# schematic.net
KiCad netlist of a schematic drawn in EAGLE
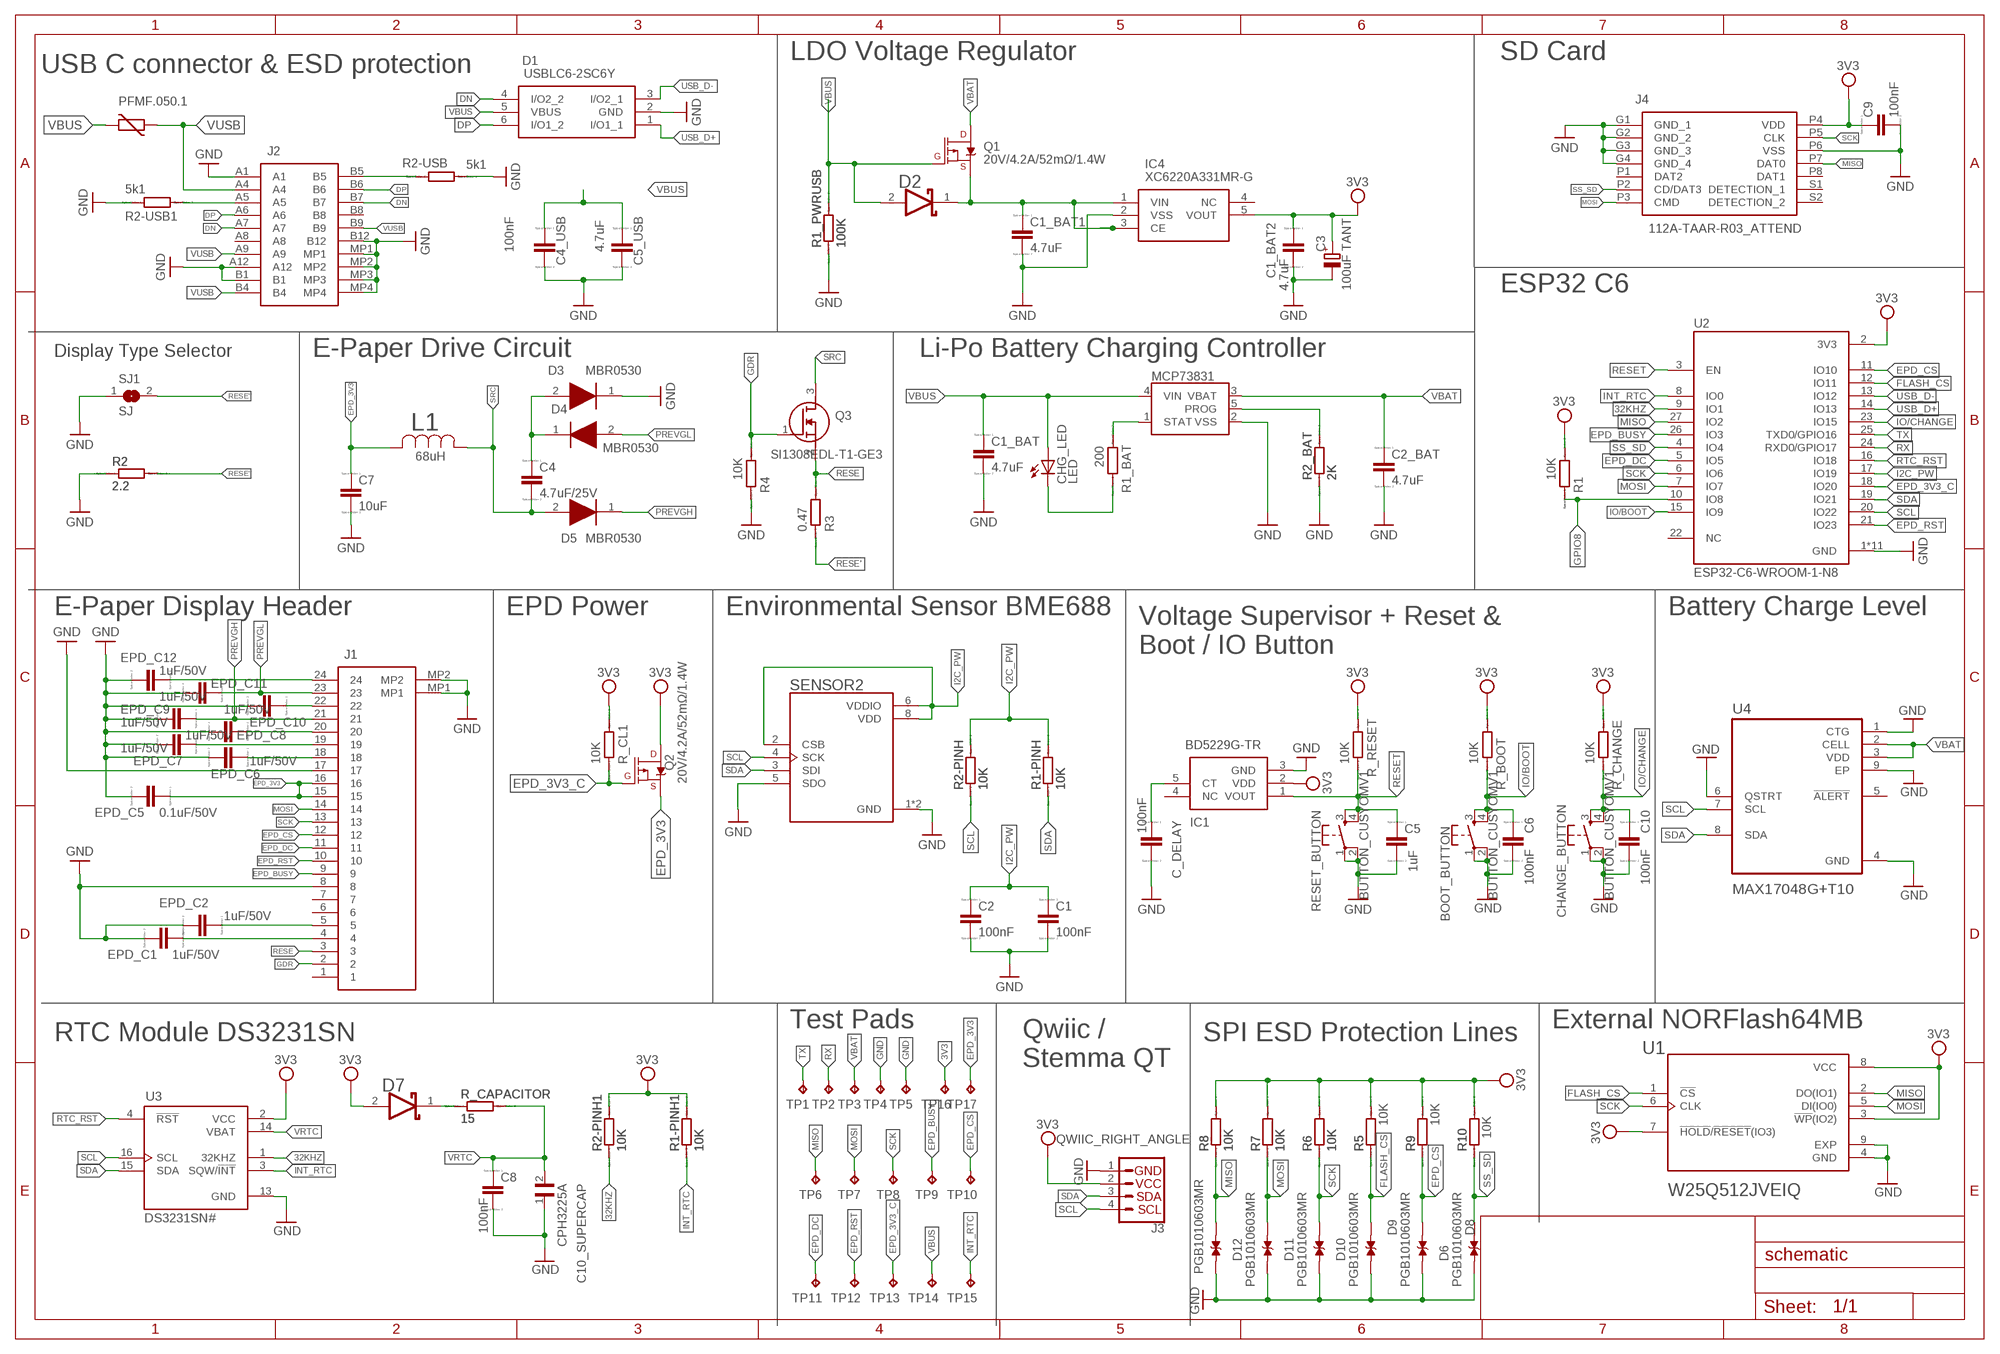
[diagram p0: schematic, sheet 1]

(export (version "E")
  (design (tool "Eeschema 10.0.6"))
  (components
    (comp (ref "BOOT_BUTTON")
      (value "BUTTON_CUSYOMV1")
      (footprint "eagle-import:MYBUTTON")
      (libsource (lib "eagle-import") (part "BUTTON_CUSYOMV1"))
    )
    (comp (ref "C1")
      (value "100nF")
      (footprint "eagle-import:EAGLE-LTSPICE_C0402")
      (libsource (lib "eagle-import") (part "EAGLE-LTSPICE_CC0402"))
    )
    (comp (ref "C1_BAT")
      (value "4.7uF")
      (footprint "eagle-import:EAGLE-LTSPICE_C0402")
      (libsource (lib "eagle-import") (part "EAGLE-LTSPICE_CC0402"))
    )
    (comp (ref "C1_BAT1")
      (value "4.7uF")
      (footprint "eagle-import:EAGLE-LTSPICE_C0402")
      (libsource (lib "eagle-import") (part "EAGLE-LTSPICE_CC0402"))
    )
    (comp (ref "C1_BAT2")
      (value "4.7uF")
      (footprint "eagle-import:EAGLE-LTSPICE_C0402")
      (libsource (lib "eagle-import") (part "EAGLE-LTSPICE_CC0402"))
    )
    (comp (ref "C2")
      (value "100nF")
      (footprint "eagle-import:EAGLE-LTSPICE_C0402")
      (libsource (lib "eagle-import") (part "EAGLE-LTSPICE_CC0402"))
    )
    (comp (ref "C2_BAT")
      (value "4.7uF")
      (footprint "eagle-import:EAGLE-LTSPICE_C0402")
      (libsource (lib "eagle-import") (part "EAGLE-LTSPICE_CC0402"))
    )
    (comp (ref "C3")
      (value "100uF TANT")
      (footprint "eagle-import:RCL_CT3528")
      (libsource (lib "eagle-import") (part "RCL_CPOL-EUCT3528"))
    )
    (comp (ref "C4")
      (value "4.7uF/25V")
      (footprint "eagle-import:EAGLE-LTSPICE_C0402")
      (libsource (lib "eagle-import") (part "EAGLE-LTSPICE_CC0402"))
    )
    (comp (ref "C4_USB")
      (value "100nF")
      (footprint "eagle-import:EAGLE-LTSPICE_C0402")
      (libsource (lib "eagle-import") (part "EAGLE-LTSPICE_CC0402"))
    )
    (comp (ref "C5")
      (value "1uF")
      (footprint "eagle-import:EAGLE-LTSPICE_C0402")
      (libsource (lib "eagle-import") (part "EAGLE-LTSPICE_CC0402"))
    )
    (comp (ref "C5_USB")
      (value "4.7uF")
      (footprint "eagle-import:EAGLE-LTSPICE_C0402")
      (libsource (lib "eagle-import") (part "EAGLE-LTSPICE_CC0402"))
    )
    (comp (ref "C6")
      (value "100nF")
      (footprint "eagle-import:EAGLE-LTSPICE_C0402")
      (libsource (lib "eagle-import") (part "EAGLE-LTSPICE_CC0402"))
    )
    (comp (ref "C7")
      (value "10uF")
      (footprint "eagle-import:EAGLE-LTSPICE_C0402")
      (libsource (lib "eagle-import") (part "EAGLE-LTSPICE_CC0402"))
    )
    (comp (ref "C8")
      (value "100nF")
      (footprint "eagle-import:EAGLE-LTSPICE_C0402")
      (libsource (lib "eagle-import") (part "EAGLE-LTSPICE_CC0402"))
    )
    (comp (ref "C9")
      (value "100nF")
      (footprint "eagle-import:EAGLE-LTSPICE_C0402")
      (libsource (lib "eagle-import") (part "EAGLE-LTSPICE_CC0402"))
    )
    (comp (ref "C10")
      (value "100nF")
      (footprint "eagle-import:EAGLE-LTSPICE_C0402")
      (libsource (lib "eagle-import") (part "EAGLE-LTSPICE_CC0402"))
    )
    (comp (ref "C10_SUPERCAP")
      (value "CPH3225A")
      (footprint "eagle-import:CAPCP3225X100N")
      (fields (field (name "MF") "Seiko Instruments"))
      (libsource (lib "eagle-import") (part "CPH3225A"))
    )
    (comp (ref "CHANGE_BUTTON")
      (value "BUTTON_CUSYOMV1")
      (footprint "eagle-import:MYBUTTON")
      (libsource (lib "eagle-import") (part "BUTTON_CUSYOMV1"))
    )
    (comp (ref "CHG_LED")
      (value "LED")
      (footprint "eagle-import:ADAFRUIT_CHIP-LED0603")
      (libsource (lib "eagle-import") (part "ADAFRUIT_LEDCHIP-LED0603"))
    )
    (comp (ref "C_DELAY")
      (value "100nF")
      (footprint "eagle-import:EAGLE-LTSPICE_C0402")
      (libsource (lib "eagle-import") (part "EAGLE-LTSPICE_CC0402"))
    )
    (comp (ref "D1")
      (value "USBLC6-2SC6Y")
      (footprint "eagle-import:SOT95P280X145-6N")
      (fields (field (name "MF") "STMicroelectronics"))
      (libsource (lib "eagle-import") (part "USBLC6-2SC6Y"))
    )
    (comp (ref "D2")
      (value "ESP32_WROVER_AVX---SD0805S020S1R0_AVX_SD0805S020S1R0_0_0AVX_SD0805S020S1R0_0_0")
      (footprint "eagle-import:ESP32_WROVER_AVX---SD0805S020S1R0_AVX_SD0805S020S1R0_0")
      (fields
        (field (name "DIGIKEY_PART_NUMBER") "478-7800-1-ND")
        (field (name "MF") "AVX")
        (field (name "MOUSER_PART_NUMBER") "581-SD0805S020S1R0")
      )
      (libsource (lib "eagle-import") (part "ESP32_WROVER_AVX---SD0805S020S1R0_AVX_SD0805S020S1R0_0_0AVX_SD0805S020S1R0_0_0"))
    )
    (comp (ref "D3")
      (value "MBR0530")
      (footprint "eagle-import:SOD3716X135N")
      (fields (field (name "MF") "ON Semiconductor"))
      (libsource (lib "eagle-import") (part "MBR0530"))
    )
    (comp (ref "D4")
      (value "MBR0530")
      (footprint "eagle-import:SOD3716X135N")
      (fields (field (name "MF") "ON Semiconductor"))
      (libsource (lib "eagle-import") (part "MBR0530"))
    )
    (comp (ref "D5")
      (value "MBR0530")
      (footprint "eagle-import:SOD3716X135N")
      (fields (field (name "MF") "ON Semiconductor"))
      (libsource (lib "eagle-import") (part "MBR0530"))
    )
    (comp (ref "D6")
      (value "PGB1010603MR")
      (footprint "eagle-import:DIOC1608X36N")
      (fields (field (name "MF") "Littelfuse Inc."))
      (libsource (lib "eagle-import") (part "PGB1010603MR"))
    )
    (comp (ref "D7")
      (value "ESP32_WROVER_AVX---SD0805S020S1R0_AVX_SD0805S020S1R0_0_0AVX_SD0805S020S1R0_0_0")
      (footprint "eagle-import:ESP32_WROVER_AVX---SD0805S020S1R0_AVX_SD0805S020S1R0_0")
      (fields
        (field (name "DIGIKEY_PART_NUMBER") "478-7800-1-ND")
        (field (name "MF") "AVX")
        (field (name "MOUSER_PART_NUMBER") "581-SD0805S020S1R0")
      )
      (libsource (lib "eagle-import") (part "ESP32_WROVER_AVX---SD0805S020S1R0_AVX_SD0805S020S1R0_0_0AVX_SD0805S020S1R0_0_0"))
    )
    (comp (ref "D8")
      (value "PGB1010603MR")
      (footprint "eagle-import:DIOC1608X36N")
      (fields (field (name "MF") "Littelfuse Inc."))
      (libsource (lib "eagle-import") (part "PGB1010603MR"))
    )
    (comp (ref "D9")
      (value "PGB1010603MR")
      (footprint "eagle-import:DIOC1608X36N")
      (fields (field (name "MF") "Littelfuse Inc."))
      (libsource (lib "eagle-import") (part "PGB1010603MR"))
    )
    (comp (ref "D10")
      (value "PGB1010603MR")
      (footprint "eagle-import:DIOC1608X36N")
      (fields (field (name "MF") "Littelfuse Inc."))
      (libsource (lib "eagle-import") (part "PGB1010603MR"))
    )
    (comp (ref "D11")
      (value "PGB1010603MR")
      (footprint "eagle-import:DIOC1608X36N")
      (fields (field (name "MF") "Littelfuse Inc."))
      (libsource (lib "eagle-import") (part "PGB1010603MR"))
    )
    (comp (ref "D12")
      (value "PGB1010603MR")
      (footprint "eagle-import:DIOC1608X36N")
      (fields (field (name "MF") "Littelfuse Inc."))
      (libsource (lib "eagle-import") (part "PGB1010603MR"))
    )
    (comp (ref "EPD_C1")
      (value "1uF/50V")
      (footprint "eagle-import:EAGLE-LTSPICE_C0402")
      (libsource (lib "eagle-import") (part "EAGLE-LTSPICE_CC0402"))
    )
    (comp (ref "EPD_C2")
      (value "1uF/50V")
      (footprint "eagle-import:EAGLE-LTSPICE_C0402")
      (libsource (lib "eagle-import") (part "EAGLE-LTSPICE_CC0402"))
    )
    (comp (ref "EPD_C5")
      (value "0.1uF/50V")
      (footprint "eagle-import:EAGLE-LTSPICE_C0402")
      (libsource (lib "eagle-import") (part "EAGLE-LTSPICE_CC0402"))
    )
    (comp (ref "EPD_C6")
      (value "1uF/50V")
      (footprint "eagle-import:EAGLE-LTSPICE_C0402")
      (libsource (lib "eagle-import") (part "EAGLE-LTSPICE_CC0402"))
    )
    (comp (ref "EPD_C7")
      (value "1uF/50V")
      (footprint "eagle-import:EAGLE-LTSPICE_C0402")
      (libsource (lib "eagle-import") (part "EAGLE-LTSPICE_CC0402"))
    )
    (comp (ref "EPD_C8")
      (value "1uF/50V")
      (footprint "eagle-import:EAGLE-LTSPICE_C0402")
      (libsource (lib "eagle-import") (part "EAGLE-LTSPICE_CC0402"))
    )
    (comp (ref "EPD_C9")
      (value "1uF/50V")
      (footprint "eagle-import:EAGLE-LTSPICE_C0402")
      (libsource (lib "eagle-import") (part "EAGLE-LTSPICE_CC0402"))
    )
    (comp (ref "EPD_C10")
      (value "1uF/50V")
      (footprint "eagle-import:EAGLE-LTSPICE_C0402")
      (libsource (lib "eagle-import") (part "EAGLE-LTSPICE_CC0402"))
    )
    (comp (ref "EPD_C11")
      (value "1uF/50V")
      (footprint "eagle-import:EAGLE-LTSPICE_C0402")
      (libsource (lib "eagle-import") (part "EAGLE-LTSPICE_CC0402"))
    )
    (comp (ref "EPD_C12")
      (value "1uF/50V")
      (footprint "eagle-import:EAGLE-LTSPICE_C0402")
      (libsource (lib "eagle-import") (part "EAGLE-LTSPICE_CC0402"))
    )
    (comp (ref "IC1")
      (value "BD5229G-TR")
      (footprint "eagle-import:SOT95P280X125-5N")
      (fields (field (name "MOUSER_PART_NUMBER") "755-BD5229G-TR"))
      (libsource (lib "eagle-import") (part "BD5229G-TR"))
    )
    (comp (ref "IC4")
      (value "XC6220A331MR-G")
      (footprint "eagle-import:SOT95P280X120-5N")
      (fields (field (name "MOUSER_PART_NUMBER") "865-XC6220A331MR-G"))
      (libsource (lib "eagle-import") (part "XC6220A331MR-G"))
    )
    (comp (ref "J1")
      (value "FH34SRJ-24S-0.5SH_99_")
      (footprint "eagle-import:FH34SRJ24S05SH99")
      (fields
        (field (name "MANUFACTURER_PART_NUMBER") "FH34SRJ-24S-0.5SH(99)")
        (field (name "MOUSER_PART_NUMBER") "798-FH34SRJ24S05SH99")
      )
      (libsource (lib "eagle-import") (part "FH34SRJ-24S-0.5SH_99_"))
    )
    (comp (ref "J2")
      (value "SAMACSYS_PARTS_USB4110-GF-A")
      (footprint "eagle-import:SAMACSYS_PARTS_USB4110GFA")
      (fields
        (field (name "MANUFACTURER_PART_NUMBER") "USB4110-GF-A")
        (field (name "MOUSER_PART_NUMBER") "640-USB4110-GF-A")
      )
      (libsource (lib "eagle-import") (part "SAMACSYS_PARTS_USB4110-GF-A"))
    )
    (comp (ref "J3")
      (value "QWIIC_RIGHT_ANGLE")
      (footprint "eagle-import:JST04_1MM_RA")
      (libsource (lib "eagle-import") (part "QWIIC_CONNECTORJS-1MM"))
    )
    (comp (ref "J4")
      (value "112A-TAAR-R03_ATTEND")
      (footprint "eagle-import:112ATAARR03ATTEND")
      (fields (field (name "MANUFACTURER_PART_NUMBER") "112A-TAAR-R03 ATTEND"))
      (libsource (lib "eagle-import") (part "112A-TAAR-R03_ATTEND"))
    )
    (comp (ref "L1")
      (value "68uH")
      (footprint "eagle-import:IND_4828-WE-TPC_WRE")
      (fields
        (field (name "MANUFACTURER_PART_NUMBER") "744043680")
        (field (name "COPYRIGHT") "Copyright (C) 2024 Ultra Librarian. All rights reserved.")
      )
      (libsource (lib "eagle-import") (part "744043680IND_4828-WE-TPC_WRE"))
    )
    (comp (ref "MCP73831")
      (value "ESP32_WROVER_SPARKFUN-IC-POWER_MCP73831")
      (footprint "eagle-import:ESP32_WROVER_SPARKFUN-IC-POWER_SOT23-5")
      (libsource (lib "eagle-import") (part "ESP32_WROVER_SPARKFUN-IC-POWER_MCP73831"))
    )
    (comp (ref "PFMF.050.1")
      (value "ESP32C6_VARISTORCN1812")
      (footprint "eagle-import:ESP32C6_VARISTOR_CT_CN1812")
      (libsource (lib "eagle-import") (part "ESP32C6_VARISTORCN1812"))
    )
    (comp (ref "Q1")
      (value "20V/4.2A/52mΩ/1.4W")
      (footprint "eagle-import:ESP32_WROVER_SPARKFUN-DISCRETESEMI_SOT23-3")
      (libsource (lib "eagle-import") (part "ESP32_WROVER_SPARKFUN-DISCRETESEMI_MOSFET_PCH-DMG2305UX-7"))
    )
    (comp (ref "Q2")
      (value "20V/4.2A/52mΩ/1.4W")
      (footprint "eagle-import:ESP32_WROVER_SPARKFUN-DISCRETESEMI_SOT23-3")
      (libsource (lib "eagle-import") (part "ESP32_WROVER_SPARKFUN-DISCRETESEMI_MOSFET_PCH-DMG2305UX-7"))
    )
    (comp (ref "Q3")
      (value "SI1308EDL-T1-GE3")
      (footprint "eagle-import:SOT65P210X110-3N")
      (fields (field (name "MF") "Vishay Siliconix"))
      (libsource (lib "eagle-import") (part "SI1308EDL-T1-GE3"))
    )
    (comp (ref "R1")
      (value "10K")
      (footprint "eagle-import:ESP32_WROVER_EAGLE-LTSPICE_R0402")
      (libsource (lib "eagle-import") (part "ESP32_WROVER_EAGLE-LTSPICE_RR0402"))
    )
    (comp (ref "R1-PINH")
      (value "10K")
      (footprint "eagle-import:ESP32_WROVER_EAGLE-LTSPICE_R0402")
      (libsource (lib "eagle-import") (part "ESP32_WROVER_EAGLE-LTSPICE_RR0402"))
    )
    (comp (ref "R1-PINH1")
      (value "10K")
      (footprint "eagle-import:ESP32_WROVER_EAGLE-LTSPICE_R0402")
      (libsource (lib "eagle-import") (part "ESP32_WROVER_EAGLE-LTSPICE_RR0402"))
    )
    (comp (ref "R1_BAT")
      (value "200")
      (footprint "eagle-import:ESP32_WROVER_EAGLE-LTSPICE_R0402")
      (libsource (lib "eagle-import") (part "ESP32_WROVER_EAGLE-LTSPICE_RR0402"))
    )
    (comp (ref "R1_PWRUSB")
      (value "100K")
      (footprint "eagle-import:ESP32_WROVER_EAGLE-LTSPICE_R0402")
      (libsource (lib "eagle-import") (part "ESP32_WROVER_EAGLE-LTSPICE_RR0402"))
    )
    (comp (ref "R2")
      (value "2.2")
      (footprint "eagle-import:ESP32_WROVER_EAGLE-LTSPICE_R0402")
      (libsource (lib "eagle-import") (part "ESP32_WROVER_EAGLE-LTSPICE_RR0402"))
    )
    (comp (ref "R2-PINH")
      (value "10K")
      (footprint "eagle-import:ESP32_WROVER_EAGLE-LTSPICE_R0402")
      (libsource (lib "eagle-import") (part "ESP32_WROVER_EAGLE-LTSPICE_RR0402"))
    )
    (comp (ref "R2-PINH1")
      (value "10K")
      (footprint "eagle-import:ESP32_WROVER_EAGLE-LTSPICE_R0402")
      (libsource (lib "eagle-import") (part "ESP32_WROVER_EAGLE-LTSPICE_RR0402"))
    )
    (comp (ref "R2-USB")
      (value "5k1")
      (footprint "eagle-import:ESP32_WROVER_EAGLE-LTSPICE_R0402")
      (libsource (lib "eagle-import") (part "ESP32_WROVER_EAGLE-LTSPICE_RR0402"))
    )
    (comp (ref "R2-USB1")
      (value "5k1")
      (footprint "eagle-import:ESP32_WROVER_EAGLE-LTSPICE_R0402")
      (libsource (lib "eagle-import") (part "ESP32_WROVER_EAGLE-LTSPICE_RR0402"))
    )
    (comp (ref "R2_BAT")
      (value "2K")
      (footprint "eagle-import:ESP32_WROVER_EAGLE-LTSPICE_R0402")
      (libsource (lib "eagle-import") (part "ESP32_WROVER_EAGLE-LTSPICE_RR0402"))
    )
    (comp (ref "R3")
      (value "0.47")
      (footprint "eagle-import:ESP32_WROVER_EAGLE-LTSPICE_R0402")
      (libsource (lib "eagle-import") (part "ESP32_WROVER_EAGLE-LTSPICE_RR0402"))
    )
    (comp (ref "R4")
      (value "10K")
      (footprint "eagle-import:ESP32_WROVER_EAGLE-LTSPICE_R0402")
      (libsource (lib "eagle-import") (part "ESP32_WROVER_EAGLE-LTSPICE_RR0402"))
    )
    (comp (ref "R5")
      (value "10K")
      (footprint "eagle-import:ESP32_WROVER_EAGLE-LTSPICE_R0402")
      (libsource (lib "eagle-import") (part "ESP32_WROVER_EAGLE-LTSPICE_RR0402"))
    )
    (comp (ref "R6")
      (value "10K")
      (footprint "eagle-import:ESP32_WROVER_EAGLE-LTSPICE_R0402")
      (libsource (lib "eagle-import") (part "ESP32_WROVER_EAGLE-LTSPICE_RR0402"))
    )
    (comp (ref "R7")
      (value "10K")
      (footprint "eagle-import:ESP32_WROVER_EAGLE-LTSPICE_R0402")
      (libsource (lib "eagle-import") (part "ESP32_WROVER_EAGLE-LTSPICE_RR0402"))
    )
    (comp (ref "R8")
      (value "10K")
      (footprint "eagle-import:ESP32_WROVER_EAGLE-LTSPICE_R0402")
      (libsource (lib "eagle-import") (part "ESP32_WROVER_EAGLE-LTSPICE_RR0402"))
    )
    (comp (ref "R9")
      (value "10K")
      (footprint "eagle-import:ESP32_WROVER_EAGLE-LTSPICE_R0402")
      (libsource (lib "eagle-import") (part "ESP32_WROVER_EAGLE-LTSPICE_RR0402"))
    )
    (comp (ref "R10")
      (value "10K")
      (footprint "eagle-import:ESP32_WROVER_EAGLE-LTSPICE_R0402")
      (libsource (lib "eagle-import") (part "ESP32_WROVER_EAGLE-LTSPICE_RR0402"))
    )
    (comp (ref "RESET_BUTTON")
      (value "BUTTON_CUSYOMV1")
      (footprint "eagle-import:MYBUTTON")
      (libsource (lib "eagle-import") (part "BUTTON_CUSYOMV1"))
    )
    (comp (ref "R_BOOT")
      (value "10K")
      (footprint "eagle-import:ESP32_WROVER_EAGLE-LTSPICE_R0402")
      (libsource (lib "eagle-import") (part "ESP32_WROVER_EAGLE-LTSPICE_RR0402"))
    )
    (comp (ref "R_CAPACITOR")
      (value "15")
      (footprint "eagle-import:ESP32_WROVER_EAGLE-LTSPICE_R0402")
      (libsource (lib "eagle-import") (part "ESP32_WROVER_EAGLE-LTSPICE_RR0402"))
    )
    (comp (ref "R_CHANGE")
      (value "10K")
      (footprint "eagle-import:ESP32_WROVER_EAGLE-LTSPICE_R0402")
      (libsource (lib "eagle-import") (part "ESP32_WROVER_EAGLE-LTSPICE_RR0402"))
    )
    (comp (ref "R_CL1")
      (value "10K")
      (footprint "eagle-import:ESP32_WROVER_EAGLE-LTSPICE_R0402")
      (libsource (lib "eagle-import") (part "ESP32_WROVER_EAGLE-LTSPICE_RR0402"))
    )
    (comp (ref "R_RESET")
      (value "10K")
      (footprint "eagle-import:ESP32_WROVER_EAGLE-LTSPICE_R0402")
      (libsource (lib "eagle-import") (part "ESP32_WROVER_EAGLE-LTSPICE_RR0402"))
    )
    (comp (ref "SENSOR2")
      (value "ESP32_WROVER_BME680_BME680")
      (footprint "eagle-import:ESP32_WROVER_BME680_PSON80P300X300X100-8N")
      (fields (field (name "MF") "Bosch Sensortec") (field (name "MP") "BME680"))
      (libsource (lib "eagle-import") (part "ESP32_WROVER_BME680_BME680"))
    )
    (comp (ref "SJ1") (value "SJ") (footprint "eagle-import:SJ") (libsource (lib "eagle-import") (part "SJ")))
    (comp (ref "TP1")
      (value "TPTP20R")
      (footprint "eagle-import:TP20R")
      (libsource (lib "eagle-import") (part "TPTP20R"))
    )
    (comp (ref "TP2")
      (value "TPTP20R")
      (footprint "eagle-import:TP20R")
      (libsource (lib "eagle-import") (part "TPTP20R"))
    )
    (comp (ref "TP3")
      (value "TPTP20R")
      (footprint "eagle-import:TP20R")
      (libsource (lib "eagle-import") (part "TPTP20R"))
    )
    (comp (ref "TP4")
      (value "TPTP20R")
      (footprint "eagle-import:TP20R")
      (libsource (lib "eagle-import") (part "TPTP20R"))
    )
    (comp (ref "TP5")
      (value "TPTP20R")
      (footprint "eagle-import:TP20R")
      (libsource (lib "eagle-import") (part "TPTP20R"))
    )
    (comp (ref "TP6")
      (value "TPTP20R")
      (footprint "eagle-import:TP20R")
      (libsource (lib "eagle-import") (part "TPTP20R"))
    )
    (comp (ref "TP7")
      (value "TPTP20R")
      (footprint "eagle-import:TP20R")
      (libsource (lib "eagle-import") (part "TPTP20R"))
    )
    (comp (ref "TP8")
      (value "TPTP20R")
      (footprint "eagle-import:TP20R")
      (libsource (lib "eagle-import") (part "TPTP20R"))
    )
    (comp (ref "TP9")
      (value "TPTP20R")
      (footprint "eagle-import:TP20R")
      (libsource (lib "eagle-import") (part "TPTP20R"))
    )
    (comp (ref "TP10")
      (value "TPTP20R")
      (footprint "eagle-import:TP20R")
      (libsource (lib "eagle-import") (part "TPTP20R"))
    )
    (comp (ref "TP11")
      (value "TPTP20R")
      (footprint "eagle-import:TP20R")
      (libsource (lib "eagle-import") (part "TPTP20R"))
    )
    (comp (ref "TP12")
      (value "TPTP20R")
      (footprint "eagle-import:TP20R")
      (libsource (lib "eagle-import") (part "TPTP20R"))
    )
    (comp (ref "TP13")
      (value "TPTP20R")
      (footprint "eagle-import:TP20R")
      (libsource (lib "eagle-import") (part "TPTP20R"))
    )
    (comp (ref "TP14")
      (value "TPTP20R")
      (footprint "eagle-import:TP20R")
      (libsource (lib "eagle-import") (part "TPTP20R"))
    )
    (comp (ref "TP15")
      (value "TPTP20R")
      (footprint "eagle-import:TP20R")
      (libsource (lib "eagle-import") (part "TPTP20R"))
    )
    (comp (ref "TP16")
      (value "TPTP20R")
      (footprint "eagle-import:TP20R")
      (libsource (lib "eagle-import") (part "TPTP20R"))
    )
    (comp (ref "TP17")
      (value "TPTP20R")
      (footprint "eagle-import:TP20R")
      (libsource (lib "eagle-import") (part "TPTP20R"))
    )
    (comp (ref "U1")
      (value "W25Q512JVEIQ")
      (footprint "eagle-import:SON127P600X800X80-9N")
      (fields (field (name "MF") "Winbond Electronics"))
      (libsource (lib "eagle-import") (part "W25Q512JVEIQ"))
    )
    (comp (ref "U2")
      (value "ESP32-C6-WROOM-1-N8")
      (footprint "eagle-import:XCVR_ESP32-C6-WROOM-1-N8")
      (fields (field (name "MF") "Espressif Systems"))
      (libsource (lib "eagle-import") (part "ESP32-C6-WROOM-1-N8"))
    )
    (comp (ref "U3")
      (value "DS3231SN#")
      (footprint "eagle-import:SOIC127P1032X265-16N")
      (fields (field (name "MF") "Analog Devices"))
      (libsource (lib "eagle-import") (part "DS3231SN#"))
    )
    (comp (ref "U4")
      (value "MAX17048G+T10")
      (footprint "eagle-import:SON50P200X200X80-9N")
      (fields (field (name "MF") "Analog Devices"))
      (libsource (lib "eagle-import") (part "MAX17048G+T10"))
    )
  )
  (nets
    (net (code "1") (name "3V3") (class "Default")
      (node (ref "C1_BAT2") (pin "1") (pinfunction "1_1") (pintype "passive"))
      (node (ref "C3") (pin "+") (pinfunction "+_+") (pintype "passive"))
      (node (ref "C9") (pin "1") (pinfunction "1_1") (pintype "passive"))
      (node (ref "D7") (pin "2") (pinfunction "ANODE_2") (pintype "bidirectional"))
      (node (ref "IC1") (pin "2") (pinfunction "VDD_2") (pintype "bidirectional"))
      (node (ref "IC4") (pin "5") (pinfunction "VOUT_5") (pintype "bidirectional"))
      (node (ref "J3") (pin "2") (pinfunction "2_2") (pintype "power_in"))
      (node (ref "J4") (pin "P4") (pinfunction "VDD_P4") (pintype "bidirectional"))
      (node (ref "Q2") (pin "3") (pinfunction "D_3") (pintype "bidirectional"))
      (node (ref "R1") (pin "2") (pinfunction "2_2") (pintype "passive"))
      (node (ref "R1-PINH1") (pin "2") (pinfunction "2_2") (pintype "passive"))
      (node (ref "R10") (pin "2") (pinfunction "2_2") (pintype "passive"))
      (node (ref "R2-PINH1") (pin "2") (pinfunction "2_2") (pintype "passive"))
      (node (ref "R5") (pin "2") (pinfunction "2_2") (pintype "passive"))
      (node (ref "R6") (pin "2") (pinfunction "2_2") (pintype "passive"))
      (node (ref "R7") (pin "2") (pinfunction "2_2") (pintype "passive"))
      (node (ref "R8") (pin "2") (pinfunction "2_2") (pintype "passive"))
      (node (ref "R9") (pin "2") (pinfunction "2_2") (pintype "passive"))
      (node (ref "R_BOOT") (pin "2") (pinfunction "2_2") (pintype "passive"))
      (node (ref "R_CHANGE") (pin "2") (pinfunction "2_2") (pintype "passive"))
      (node (ref "R_CL1") (pin "2") (pinfunction "2_2") (pintype "passive"))
      (node (ref "R_RESET") (pin "2") (pinfunction "2_2") (pintype "passive"))
      (node (ref "TP16") (pin "TP") (pinfunction "TP_TP") (pintype "input"))
      (node (ref "U1") (pin "3") (pinfunction "~{WP}(IO2)_3") (pintype "bidirectional"))
      (node (ref "U1") (pin "7") (pinfunction "~{HOLD}/~{RESET}(IO3)_7") (pintype "bidirectional"))
      (node (ref "U1") (pin "8") (pinfunction "VCC_8") (pintype "power_in"))
      (node (ref "U2") (pin "2") (pinfunction "3V3_2") (pintype "power_in"))
      (node (ref "U3") (pin "2") (pinfunction "VCC_2") (pintype "power_in"))
    )
    (net (code "2") (name "32KHZ") (class "Default")
      (node (ref "R2-PINH1") (pin "1") (pinfunction "1_1") (pintype "passive"))
      (node (ref "U2") (pin "9") (pinfunction "IO1_9") (pintype "bidirectional"))
      (node (ref "U3") (pin "1") (pinfunction "32KHZ_1") (pintype "output"))
    )
    (net (code "3") (name "DN") (class "Default")
      (node (ref "D1") (pin "4") (pinfunction "I/O2_2_4") (pintype "bidirectional"))
      (node (ref "J2") (pin "A7") (pinfunction "A7_A7") (pintype "bidirectional"))
      (node (ref "J2") (pin "B7") (pinfunction "B7_B7") (pintype "bidirectional"))
    )
    (net (code "4") (name "DP") (class "Default")
      (node (ref "D1") (pin "6") (pinfunction "I/O1_2_6") (pintype "bidirectional"))
      (node (ref "J2") (pin "A6") (pinfunction "A6_A6") (pintype "bidirectional"))
      (node (ref "J2") (pin "B6") (pinfunction "B6_B6") (pintype "bidirectional"))
    )
    (net (code "5") (name "EPD_3V3") (class "Default")
      (node (ref "C7") (pin "1") (pinfunction "1_1") (pintype "passive"))
      (node (ref "EPD_C5") (pin "1") (pinfunction "1_1") (pintype "passive"))
      (node (ref "J1") (pin "15") (pinfunction "15_15") (pintype "bidirectional"))
      (node (ref "J1") (pin "16") (pinfunction "16_16") (pintype "bidirectional"))
      (node (ref "L1") (pin "2") (pinfunction "2_2") (pintype "passive"))
      (node (ref "Q2") (pin "2") (pinfunction "S_2") (pintype "bidirectional"))
      (node (ref "TP17") (pin "TP") (pinfunction "TP_TP") (pintype "input"))
    )
    (net (code "6") (name "EPD_3V3_C") (class "Default")
      (node (ref "Q2") (pin "1") (pinfunction "G_1") (pintype "bidirectional"))
      (node (ref "R_CL1") (pin "1") (pinfunction "1_1") (pintype "passive"))
      (node (ref "TP13") (pin "TP") (pinfunction "TP_TP") (pintype "input"))
      (node (ref "U2") (pin "18") (pinfunction "IO20_18") (pintype "bidirectional"))
    )
    (net (code "7") (name "EPD_BUSY") (class "Default")
      (node (ref "J1") (pin "9") (pinfunction "9_9") (pintype "bidirectional"))
      (node (ref "TP9") (pin "TP") (pinfunction "TP_TP") (pintype "input"))
      (node (ref "U2") (pin "26") (pinfunction "IO3_26") (pintype "bidirectional"))
    )
    (net (code "8") (name "EPD_CS") (class "Default")
      (node (ref "D6") (pin "2") (pinfunction "2_2") (pintype "passive"))
      (node (ref "J1") (pin "12") (pinfunction "12_12") (pintype "bidirectional"))
      (node (ref "R9") (pin "1") (pinfunction "1_1") (pintype "passive"))
      (node (ref "TP10") (pin "TP") (pinfunction "TP_TP") (pintype "input"))
      (node (ref "U2") (pin "11") (pinfunction "IO10_11") (pintype "bidirectional"))
    )
    (net (code "9") (name "EPD_DC") (class "Default")
      (node (ref "J1") (pin "11") (pinfunction "11_11") (pintype "bidirectional"))
      (node (ref "TP11") (pin "TP") (pinfunction "TP_TP") (pintype "input"))
      (node (ref "U2") (pin "5") (pinfunction "IO5_5") (pintype "bidirectional"))
    )
    (net (code "10") (name "EPD_RST") (class "Default")
      (node (ref "J1") (pin "10") (pinfunction "10_10") (pintype "bidirectional"))
      (node (ref "TP12") (pin "TP") (pinfunction "TP_TP") (pintype "input"))
      (node (ref "U2") (pin "21") (pinfunction "IO23_21") (pintype "bidirectional"))
    )
    (net (code "11") (name "FLASH_CS") (class "Default")
      (node (ref "D9") (pin "2") (pinfunction "2_2") (pintype "passive"))
      (node (ref "R5") (pin "1") (pinfunction "1_1") (pintype "passive"))
      (node (ref "U1") (pin "1") (pinfunction "~{CS}_1") (pintype "input"))
      (node (ref "U2") (pin "12") (pinfunction "IO11_12") (pintype "bidirectional"))
    )
    (net (code "12") (name "GDR") (class "Default")
      (node (ref "J1") (pin "2") (pinfunction "2_2") (pintype "bidirectional"))
      (node (ref "Q3") (pin "1") (pinfunction "G_1") (pintype "bidirectional"))
      (node (ref "R4") (pin "2") (pinfunction "2_2") (pintype "passive"))
    )
    (net (code "13") (name "GND") (class "Default")
      (node (ref "BOOT_BUTTON") (pin "1") (pinfunction "1_1") (pintype "passive"))
      (node (ref "BOOT_BUTTON") (pin "2") (pinfunction "2_2") (pintype "passive"))
      (node (ref "C1") (pin "2") (pinfunction "2_2") (pintype "passive"))
      (node (ref "C10") (pin "2") (pinfunction "2_2") (pintype "passive"))
      (node (ref "C10_SUPERCAP") (pin "1") (pinfunction "1_1") (pintype "passive"))
      (node (ref "C1_BAT") (pin "2") (pinfunction "2_2") (pintype "passive"))
      (node (ref "C1_BAT1") (pin "2") (pinfunction "2_2") (pintype "passive"))
      (node (ref "C1_BAT2") (pin "2") (pinfunction "2_2") (pintype "passive"))
      (node (ref "C2") (pin "2") (pinfunction "2_2") (pintype "passive"))
      (node (ref "C2_BAT") (pin "2") (pinfunction "2_2") (pintype "passive"))
      (node (ref "C3") (pin "-") (pinfunction "-_-") (pintype "passive"))
      (node (ref "C4_USB") (pin "2") (pinfunction "2_2") (pintype "passive"))
      (node (ref "C5") (pin "2") (pinfunction "2_2") (pintype "passive"))
      (node (ref "C5_USB") (pin "2") (pinfunction "2_2") (pintype "passive"))
      (node (ref "C6") (pin "2") (pinfunction "2_2") (pintype "passive"))
      (node (ref "C7") (pin "2") (pinfunction "2_2") (pintype "passive"))
      (node (ref "C8") (pin "2") (pinfunction "2_2") (pintype "passive"))
      (node (ref "C9") (pin "2") (pinfunction "2_2") (pintype "passive"))
      (node (ref "CHANGE_BUTTON") (pin "1") (pinfunction "1_1") (pintype "passive"))
      (node (ref "CHANGE_BUTTON") (pin "2") (pinfunction "2_2") (pintype "passive"))
      (node (ref "C_DELAY") (pin "2") (pinfunction "2_2") (pintype "passive"))
      (node (ref "D1") (pin "2") (pinfunction "GND_2") (pintype "bidirectional"))
      (node (ref "D10") (pin "1") (pinfunction "1_1") (pintype "passive"))
      (node (ref "D11") (pin "1") (pinfunction "1_1") (pintype "passive"))
      (node (ref "D12") (pin "1") (pinfunction "1_1") (pintype "passive"))
      (node (ref "D3") (pin "1") (pinfunction "K_1") (pintype "bidirectional"))
      (node (ref "D6") (pin "1") (pinfunction "1_1") (pintype "passive"))
      (node (ref "D8") (pin "1") (pinfunction "1_1") (pintype "passive"))
      (node (ref "D9") (pin "1") (pinfunction "1_1") (pintype "passive"))
      (node (ref "EPD_C1") (pin "2") (pinfunction "2_2") (pintype "passive"))
      (node (ref "EPD_C10") (pin "2") (pinfunction "2_2") (pintype "passive"))
      (node (ref "EPD_C11") (pin "2") (pinfunction "2_2") (pintype "passive"))
      (node (ref "EPD_C12") (pin "2") (pinfunction "2_2") (pintype "passive"))
      (node (ref "EPD_C2") (pin "2") (pinfunction "2_2") (pintype "passive"))
      (node (ref "EPD_C5") (pin "2") (pinfunction "2_2") (pintype "passive"))
      (node (ref "EPD_C6") (pin "2") (pinfunction "2_2") (pintype "passive"))
      (node (ref "EPD_C7") (pin "2") (pinfunction "2_2") (pintype "passive"))
      (node (ref "EPD_C8") (pin "2") (pinfunction "2_2") (pintype "passive"))
      (node (ref "EPD_C9") (pin "2") (pinfunction "2_2") (pintype "passive"))
      (node (ref "IC1") (pin "3") (pinfunction "GND_3") (pintype "bidirectional"))
      (node (ref "IC4") (pin "2") (pinfunction "VSS_2") (pintype "bidirectional"))
      (node (ref "J1") (pin "17") (pinfunction "17_17") (pintype "bidirectional"))
      (node (ref "J1") (pin "8") (pinfunction "8_8") (pintype "bidirectional"))
      (node (ref "J1") (pin "MP1") (pinfunction "MP1_MP1") (pintype "bidirectional"))
      (node (ref "J1") (pin "MP2") (pinfunction "MP2_MP2") (pintype "bidirectional"))
      (node (ref "J2") (pin "A1") (pinfunction "A1_A1") (pintype "bidirectional"))
      (node (ref "J2") (pin "A12") (pinfunction "A12_A12") (pintype "bidirectional"))
      (node (ref "J2") (pin "B1") (pinfunction "B1_B1") (pintype "bidirectional"))
      (node (ref "J2") (pin "B12") (pinfunction "B12_B12") (pintype "bidirectional"))
      (node (ref "J2") (pin "MP1") (pinfunction "MP1_MP1") (pintype "bidirectional"))
      (node (ref "J2") (pin "MP2") (pinfunction "MP2_MP2") (pintype "bidirectional"))
      (node (ref "J2") (pin "MP3") (pinfunction "MP3_MP3") (pintype "bidirectional"))
      (node (ref "J2") (pin "MP4") (pinfunction "MP4_MP4") (pintype "bidirectional"))
      (node (ref "J3") (pin "1") (pinfunction "1_1") (pintype "power_in"))
      (node (ref "J4") (pin "G1") (pinfunction "GND_1_G1") (pintype "bidirectional"))
      (node (ref "J4") (pin "G2") (pinfunction "GND_2_G2") (pintype "bidirectional"))
      (node (ref "J4") (pin "G3") (pinfunction "GND_3_G3") (pintype "bidirectional"))
      (node (ref "J4") (pin "G4") (pinfunction "GND_4_G4") (pintype "bidirectional"))
      (node (ref "J4") (pin "P6") (pinfunction "VSS_P6") (pintype "bidirectional"))
      (node (ref "MCP73831") (pin "2") (pinfunction "VSS_2") (pintype "power_in"))
      (node (ref "R1_PWRUSB") (pin "1") (pinfunction "1_1") (pintype "passive"))
      (node (ref "R2") (pin "1") (pinfunction "1_1") (pintype "passive"))
      (node (ref "R2-USB") (pin "1") (pinfunction "1_1") (pintype "passive"))
      (node (ref "R2-USB1") (pin "1") (pinfunction "1_1") (pintype "passive"))
      (node (ref "R2_BAT") (pin "1") (pinfunction "1_1") (pintype "passive"))
      (node (ref "R4") (pin "1") (pinfunction "1_1") (pintype "passive"))
      (node (ref "RESET_BUTTON") (pin "1") (pinfunction "1_1") (pintype "passive"))
      (node (ref "RESET_BUTTON") (pin "2") (pinfunction "2_2") (pintype "passive"))
      (node (ref "SENSOR2") (pin "1") (pinfunction "GND_1") (pintype "power_in"))
      (node (ref "SENSOR2") (pin "5") (pinfunction "SDO_5") (pintype "bidirectional"))
      (node (ref "SENSOR2") (pin "7") (pinfunction "GND_7") (pintype "power_in"))
      (node (ref "SJ1") (pin "1") (pinfunction "1_1") (pintype "passive"))
      (node (ref "TP4") (pin "TP") (pinfunction "TP_TP") (pintype "input"))
      (node (ref "TP5") (pin "TP") (pinfunction "TP_TP") (pintype "input"))
      (node (ref "U1") (pin "4") (pinfunction "GND_4") (pintype "power_in"))
      (node (ref "U1") (pin "9") (pinfunction "EXP_9") (pintype "passive"))
      (node (ref "U2") (pin "1") (pinfunction "GND_1") (pintype "power_in"))
      (node (ref "U2") (pin "28") (pinfunction "GND_28") (pintype "power_in"))
      (node (ref "U2") (pin "29_1") (pinfunction "GND_29_1") (pintype "power_in"))
      (node (ref "U2") (pin "29_2") (pinfunction "GND_29_2") (pintype "power_in"))
      (node (ref "U2") (pin "29_3") (pinfunction "GND_29_3") (pintype "power_in"))
      (node (ref "U2") (pin "29_4") (pinfunction "GND_29_4") (pintype "power_in"))
      (node (ref "U2") (pin "29_5") (pinfunction "GND_29_5") (pintype "power_in"))
      (node (ref "U2") (pin "29_6") (pinfunction "GND_29_6") (pintype "power_in"))
      (node (ref "U2") (pin "29_7") (pinfunction "GND_29_7") (pintype "power_in"))
      (node (ref "U2") (pin "29_8") (pinfunction "GND_29_8") (pintype "power_in"))
      (node (ref "U2") (pin "29_9") (pinfunction "GND_29_9") (pintype "power_in"))
      (node (ref "U3") (pin "13") (pinfunction "GND_13") (pintype "power_in"))
      (node (ref "U4") (pin "1") (pinfunction "CTG_1") (pintype "power_in"))
      (node (ref "U4") (pin "4") (pinfunction "GND_4") (pintype "power_in"))
      (node (ref "U4") (pin "6") (pinfunction "QSTRT_6") (pintype "input"))
      (node (ref "U4") (pin "9") (pinfunction "EP_9") (pintype "power_in"))
    )
    (net (code "14") (name "GPIO8") (class "Default")
      (node (ref "R1") (pin "1") (pinfunction "1_1") (pintype "passive"))
      (node (ref "U2") (pin "10") (pinfunction "IO8_10") (pintype "bidirectional"))
    )
    (net (code "15") (name "I2C_PW") (class "Default")
      (node (ref "C1") (pin "1") (pinfunction "1_1") (pintype "passive"))
      (node (ref "C2") (pin "1") (pinfunction "1_1") (pintype "passive"))
      (node (ref "R1-PINH") (pin "2") (pinfunction "2_2") (pintype "passive"))
      (node (ref "R2-PINH") (pin "2") (pinfunction "2_2") (pintype "passive"))
      (node (ref "SENSOR2") (pin "2") (pinfunction "CSB_2") (pintype "input"))
      (node (ref "SENSOR2") (pin "6") (pinfunction "VDDIO_6") (pintype "power_in"))
      (node (ref "SENSOR2") (pin "8") (pinfunction "VDD_8") (pintype "power_in"))
      (node (ref "U2") (pin "17") (pinfunction "IO19_17") (pintype "bidirectional"))
    )
    (net (code "16") (name "INT_RTC") (class "Default")
      (node (ref "R1-PINH1") (pin "1") (pinfunction "1_1") (pintype "passive"))
      (node (ref "TP15") (pin "TP") (pinfunction "TP_TP") (pintype "input"))
      (node (ref "U2") (pin "8") (pinfunction "IO0_8") (pintype "bidirectional"))
      (node (ref "U3") (pin "3") (pinfunction "SQW/~{INT}_3") (pintype "output"))
    )
    (net (code "17") (name "IO{slash}BOOT") (class "Default")
      (node (ref "BOOT_BUTTON") (pin "3") (pinfunction "3_3") (pintype "passive"))
      (node (ref "BOOT_BUTTON") (pin "4") (pinfunction "4_4") (pintype "passive"))
      (node (ref "C6") (pin "1") (pinfunction "1_1") (pintype "passive"))
      (node (ref "R_BOOT") (pin "1") (pinfunction "1_1") (pintype "passive"))
      (node (ref "U2") (pin "15") (pinfunction "IO9_15") (pintype "bidirectional"))
    )
    (net (code "18") (name "IO{slash}CHANGE") (class "Default")
      (node (ref "C10") (pin "1") (pinfunction "1_1") (pintype "passive"))
      (node (ref "CHANGE_BUTTON") (pin "3") (pinfunction "3_3") (pintype "passive"))
      (node (ref "CHANGE_BUTTON") (pin "4") (pinfunction "4_4") (pintype "passive"))
      (node (ref "R_CHANGE") (pin "1") (pinfunction "1_1") (pintype "passive"))
      (node (ref "U2") (pin "23") (pinfunction "IO15_23") (pintype "bidirectional"))
    )
    (net (code "19") (name "MISO") (class "Default")
      (node (ref "D12") (pin "2") (pinfunction "2_2") (pintype "passive"))
      (node (ref "J4") (pin "P7") (pinfunction "DAT0_P7") (pintype "bidirectional"))
      (node (ref "R8") (pin "1") (pinfunction "1_1") (pintype "passive"))
      (node (ref "TP6") (pin "TP") (pinfunction "TP_TP") (pintype "input"))
      (node (ref "U1") (pin "2") (pinfunction "DO(IO1)_2") (pintype "bidirectional"))
      (node (ref "U2") (pin "27") (pinfunction "IO2_27") (pintype "bidirectional"))
    )
    (net (code "20") (name "MOSI") (class "Default")
      (node (ref "D11") (pin "2") (pinfunction "2_2") (pintype "passive"))
      (node (ref "J1") (pin "14") (pinfunction "14_14") (pintype "bidirectional"))
      (node (ref "J4") (pin "P3") (pinfunction "CMD_P3") (pintype "bidirectional"))
      (node (ref "R7") (pin "1") (pinfunction "1_1") (pintype "passive"))
      (node (ref "TP7") (pin "TP") (pinfunction "TP_TP") (pintype "input"))
      (node (ref "U1") (pin "5") (pinfunction "DI(IO0)_5") (pintype "bidirectional"))
      (node (ref "U2") (pin "7") (pinfunction "IO7_7") (pintype "bidirectional"))
    )
    (net (code "21") (name "Net-(CHG_LED-PadC)") (class "Default")
      (node (ref "CHG_LED") (pin "C") (pinfunction "C_C") (pintype "passive"))
      (node (ref "R1_BAT") (pin "1") (pinfunction "1_1") (pintype "passive"))
    )
    (net (code "22") (name "Net-(D2-CATHODE)") (class "Default")
      (node (ref "C1_BAT1") (pin "1") (pinfunction "1_1") (pintype "passive"))
      (node (ref "D2") (pin "1") (pinfunction "CATHODE_1") (pintype "bidirectional"))
      (node (ref "IC4") (pin "1") (pinfunction "VIN_1") (pintype "bidirectional"))
      (node (ref "IC4") (pin "3") (pinfunction "CE_3") (pintype "bidirectional"))
      (node (ref "Q1") (pin "2") (pinfunction "S_2") (pintype "bidirectional"))
    )
    (net (code "23") (name "Net-(D3-A)") (class "Default")
      (node (ref "C4") (pin "1") (pinfunction "1_1") (pintype "passive"))
      (node (ref "D3") (pin "2") (pinfunction "A_2") (pintype "bidirectional"))
      (node (ref "D4") (pin "1") (pinfunction "K_1") (pintype "bidirectional"))
    )
    (net (code "24") (name "Net-(D7-CATHODE)") (class "Default")
      (node (ref "D7") (pin "1") (pinfunction "CATHODE_1") (pintype "bidirectional"))
      (node (ref "R_CAPACITOR") (pin "1") (pinfunction "1_1") (pintype "passive"))
    )
    (net (code "25") (name "Net-(EPD_C1-Pad1)") (class "Default")
      (node (ref "EPD_C1") (pin "1") (pinfunction "1_1") (pintype "passive"))
      (node (ref "J1") (pin "4") (pinfunction "4_4") (pintype "bidirectional"))
    )
    (net (code "26") (name "Net-(EPD_C2-Pad1)") (class "Default")
      (node (ref "EPD_C2") (pin "1") (pinfunction "1_1") (pintype "passive"))
      (node (ref "J1") (pin "5") (pinfunction "5_5") (pintype "bidirectional"))
    )
    (net (code "27") (name "Net-(EPD_C6-Pad1)") (class "Default")
      (node (ref "EPD_C6") (pin "1") (pinfunction "1_1") (pintype "passive"))
      (node (ref "J1") (pin "18") (pinfunction "18_18") (pintype "bidirectional"))
    )
    (net (code "28") (name "Net-(EPD_C7-Pad1)") (class "Default")
      (node (ref "EPD_C7") (pin "1") (pinfunction "1_1") (pintype "passive"))
      (node (ref "J1") (pin "19") (pinfunction "19_19") (pintype "bidirectional"))
    )
    (net (code "29") (name "Net-(EPD_C8-Pad1)") (class "Default")
      (node (ref "EPD_C8") (pin "1") (pinfunction "1_1") (pintype "passive"))
      (node (ref "J1") (pin "20") (pinfunction "20_20") (pintype "bidirectional"))
    )
    (net (code "30") (name "Net-(EPD_C10-Pad1)") (class "Default")
      (node (ref "EPD_C10") (pin "1") (pinfunction "1_1") (pintype "passive"))
      (node (ref "J1") (pin "22") (pinfunction "22_22") (pintype "bidirectional"))
    )
    (net (code "31") (name "Net-(EPD_C12-Pad1)") (class "Default")
      (node (ref "EPD_C12") (pin "1") (pinfunction "1_1") (pintype "passive"))
      (node (ref "J1") (pin "24") (pinfunction "24_24") (pintype "bidirectional"))
    )
    (net (code "32") (name "Net-(IC1-CT)") (class "Default")
      (node (ref "C_DELAY") (pin "1") (pinfunction "1_1") (pintype "passive"))
      (node (ref "IC1") (pin "5") (pinfunction "CT_5") (pintype "bidirectional"))
    )
    (net (code "33") (name "Net-(J2-PadA5)") (class "Default")
      (node (ref "J2") (pin "A5") (pinfunction "A5_A5") (pintype "bidirectional"))
      (node (ref "R2-USB1") (pin "2") (pinfunction "2_2") (pintype "passive"))
    )
    (net (code "34") (name "Net-(J2-PadB5)") (class "Default")
      (node (ref "J2") (pin "B5") (pinfunction "B5_B5") (pintype "bidirectional"))
      (node (ref "R2-USB") (pin "2") (pinfunction "2_2") (pintype "passive"))
    )
    (net (code "35") (name "Net-(MCP73831-PROG)") (class "Default")
      (node (ref "MCP73831") (pin "5") (pinfunction "PROG_5") (pintype "input"))
      (node (ref "R2_BAT") (pin "2") (pinfunction "2_2") (pintype "passive"))
    )
    (net (code "36") (name "Net-(MCP73831-STAT)") (class "Default")
      (node (ref "MCP73831") (pin "1") (pinfunction "STAT_1") (pintype "output"))
      (node (ref "R1_BAT") (pin "2") (pinfunction "2_2") (pintype "passive"))
    )
    (net (code "37") (name "PREVGH") (class "Default")
      (node (ref "D5") (pin "1") (pinfunction "K_1") (pintype "bidirectional"))
      (node (ref "EPD_C9") (pin "1") (pinfunction "1_1") (pintype "passive"))
      (node (ref "J1") (pin "21") (pinfunction "21_21") (pintype "bidirectional"))
    )
    (net (code "38") (name "PREVGL") (class "Default")
      (node (ref "D4") (pin "2") (pinfunction "A_2") (pintype "bidirectional"))
      (node (ref "EPD_C11") (pin "1") (pinfunction "1_1") (pintype "passive"))
      (node (ref "J1") (pin "23") (pinfunction "23_23") (pintype "bidirectional"))
    )
    (net (code "39") (name "RESE") (class "Default")
      (node (ref "J1") (pin "3") (pinfunction "3_3") (pintype "bidirectional"))
      (node (ref "Q3") (pin "2") (pinfunction "S_2") (pintype "bidirectional"))
      (node (ref "R3") (pin "2") (pinfunction "2_2") (pintype "passive"))
    )
    (net (code "40") (name "RESE'") (class "Default")
      (node (ref "R2") (pin "2") (pinfunction "2_2") (pintype "passive"))
      (node (ref "R3") (pin "1") (pinfunction "1_1") (pintype "passive"))
      (node (ref "SJ1") (pin "2") (pinfunction "2_2") (pintype "passive"))
    )
    (net (code "41") (name "RESET") (class "Default")
      (node (ref "C5") (pin "1") (pinfunction "1_1") (pintype "passive"))
      (node (ref "IC1") (pin "1") (pinfunction "VOUT_1") (pintype "bidirectional"))
      (node (ref "RESET_BUTTON") (pin "3") (pinfunction "3_3") (pintype "passive"))
      (node (ref "RESET_BUTTON") (pin "4") (pinfunction "4_4") (pintype "passive"))
      (node (ref "R_RESET") (pin "1") (pinfunction "1_1") (pintype "passive"))
      (node (ref "U2") (pin "3") (pinfunction "EN_3") (pintype "input"))
    )
    (net (code "42") (name "RTC_RST") (class "Default")
      (node (ref "U2") (pin "16") (pinfunction "IO18_16") (pintype "bidirectional"))
      (node (ref "U3") (pin "4") (pinfunction "~{RST}_4") (pintype "input"))
    )
    (net (code "43") (name "RX") (class "Default")
      (node (ref "TP2") (pin "TP") (pinfunction "TP_TP") (pintype "input"))
      (node (ref "U2") (pin "24") (pinfunction "RXD0/GPIO17_24") (pintype "bidirectional"))
    )
    (net (code "44") (name "SCK") (class "Default")
      (node (ref "D10") (pin "2") (pinfunction "2_2") (pintype "passive"))
      (node (ref "J1") (pin "13") (pinfunction "13_13") (pintype "bidirectional"))
      (node (ref "J4") (pin "P5") (pinfunction "CLK_P5") (pintype "bidirectional"))
      (node (ref "R6") (pin "1") (pinfunction "1_1") (pintype "passive"))
      (node (ref "TP8") (pin "TP") (pinfunction "TP_TP") (pintype "input"))
      (node (ref "U1") (pin "6") (pinfunction "CLK_6") (pintype "input"))
      (node (ref "U2") (pin "6") (pinfunction "IO6_6") (pintype "bidirectional"))
    )
    (net (code "45") (name "SCL") (class "Default")
      (node (ref "J3") (pin "4") (pinfunction "4_4") (pintype "passive"))
      (node (ref "R2-PINH") (pin "1") (pinfunction "1_1") (pintype "passive"))
      (node (ref "SENSOR2") (pin "4") (pinfunction "SCK_4") (pintype "input"))
      (node (ref "U2") (pin "20") (pinfunction "IO22_20") (pintype "bidirectional"))
      (node (ref "U3") (pin "16") (pinfunction "SCL_16") (pintype "input"))
      (node (ref "U4") (pin "7") (pinfunction "SCL_7") (pintype "input"))
    )
    (net (code "46") (name "SDA") (class "Default")
      (node (ref "J3") (pin "3") (pinfunction "3_3") (pintype "passive"))
      (node (ref "R1-PINH") (pin "1") (pinfunction "1_1") (pintype "passive"))
      (node (ref "SENSOR2") (pin "3") (pinfunction "SDI_3") (pintype "bidirectional"))
      (node (ref "U2") (pin "19") (pinfunction "IO21_19") (pintype "bidirectional"))
      (node (ref "U3") (pin "15") (pinfunction "SDA_15") (pintype "bidirectional"))
      (node (ref "U4") (pin "8") (pinfunction "SDA_8") (pintype "bidirectional"))
    )
    (net (code "47") (name "SRC") (class "Default")
      (node (ref "C4") (pin "2") (pinfunction "2_2") (pintype "passive"))
      (node (ref "D5") (pin "2") (pinfunction "A_2") (pintype "bidirectional"))
      (node (ref "L1") (pin "1") (pinfunction "1_1") (pintype "passive"))
      (node (ref "Q3") (pin "3") (pinfunction "D_3") (pintype "bidirectional"))
    )
    (net (code "48") (name "SS_SD") (class "Default")
      (node (ref "D8") (pin "2") (pinfunction "2_2") (pintype "passive"))
      (node (ref "J4") (pin "P2") (pinfunction "CD/DAT3_P2") (pintype "bidirectional"))
      (node (ref "R10") (pin "1") (pinfunction "1_1") (pintype "passive"))
      (node (ref "U2") (pin "4") (pinfunction "IO4_4") (pintype "bidirectional"))
    )
    (net (code "49") (name "TX") (class "Default")
      (node (ref "TP1") (pin "TP") (pinfunction "TP_TP") (pintype "input"))
      (node (ref "U2") (pin "25") (pinfunction "TXD0/GPIO16_25") (pintype "bidirectional"))
    )
    (net (code "50") (name "USB_D+") (class "Default")
      (node (ref "D1") (pin "1") (pinfunction "I/O1_1_1") (pintype "bidirectional"))
      (node (ref "U2") (pin "14") (pinfunction "IO13_14") (pintype "bidirectional"))
    )
    (net (code "51") (name "USB_D-") (class "Default")
      (node (ref "D1") (pin "3") (pinfunction "I/O2_1_3") (pintype "bidirectional"))
      (node (ref "U2") (pin "13") (pinfunction "IO12_13") (pintype "bidirectional"))
    )
    (net (code "52") (name "VBAT") (class "Default")
      (node (ref "C2_BAT") (pin "1") (pinfunction "1_1") (pintype "passive"))
      (node (ref "MCP73831") (pin "3") (pinfunction "VBAT_3") (pintype "power_in"))
      (node (ref "Q1") (pin "3") (pinfunction "D_3") (pintype "bidirectional"))
      (node (ref "TP3") (pin "TP") (pinfunction "TP_TP") (pintype "input"))
      (node (ref "U4") (pin "2") (pinfunction "CELL_2") (pintype "power_in"))
      (node (ref "U4") (pin "3") (pinfunction "VDD_3") (pintype "power_in"))
    )
    (net (code "53") (name "VBUS") (class "Default")
      (node (ref "C1_BAT") (pin "1") (pinfunction "1_1") (pintype "passive"))
      (node (ref "C4_USB") (pin "1") (pinfunction "1_1") (pintype "passive"))
      (node (ref "C5_USB") (pin "1") (pinfunction "1_1") (pintype "passive"))
      (node (ref "CHG_LED") (pin "A") (pinfunction "A_A") (pintype "passive"))
      (node (ref "D1") (pin "5") (pinfunction "VBUS_5") (pintype "bidirectional"))
      (node (ref "D2") (pin "2") (pinfunction "ANODE_2") (pintype "bidirectional"))
      (node (ref "MCP73831") (pin "4") (pinfunction "VIN_4") (pintype "power_in"))
      (node (ref "PFMF.050.1") (pin "2") (pinfunction "2_2") (pintype "passive"))
      (node (ref "Q1") (pin "1") (pinfunction "G_1") (pintype "bidirectional"))
      (node (ref "R1_PWRUSB") (pin "2") (pinfunction "2_2") (pintype "passive"))
      (node (ref "TP14") (pin "TP") (pinfunction "TP_TP") (pintype "input"))
    )
    (net (code "54") (name "VRTC") (class "Default")
      (node (ref "C10_SUPERCAP") (pin "2") (pinfunction "2_2") (pintype "passive"))
      (node (ref "C8") (pin "1") (pinfunction "1_1") (pintype "passive"))
      (node (ref "R_CAPACITOR") (pin "2") (pinfunction "2_2") (pintype "passive"))
      (node (ref "U3") (pin "14") (pinfunction "VBAT_14") (pintype "power_in"))
    )
    (net (code "55") (name "VUSB") (class "Default")
      (node (ref "J2") (pin "A4") (pinfunction "A4_A4") (pintype "bidirectional"))
      (node (ref "J2") (pin "A9") (pinfunction "A9_A9") (pintype "bidirectional"))
      (node (ref "J2") (pin "B4") (pinfunction "B4_B4") (pintype "bidirectional"))
      (node (ref "J2") (pin "B9") (pinfunction "B9_B9") (pintype "bidirectional"))
      (node (ref "PFMF.050.1") (pin "1") (pinfunction "1_1") (pintype "passive"))
    )
    (net (code "56") (name "unconnected-(IC1-NC-Pad4)") (class "Default")
      (node (ref "IC1") (pin "4") (pinfunction "NC_4") (pintype "no_connect"))
    )
    (net (code "57") (name "unconnected-(IC4-NC-Pad4)") (class "Default")
      (node (ref "IC4") (pin "4") (pinfunction "NC_4") (pintype "no_connect"))
    )
    (net (code "58") (name "unconnected-(J1-Pad1)") (class "Default")
      (node (ref "J1") (pin "1") (pinfunction "1_1") (pintype "bidirectional"))
    )
    (net (code "59") (name "unconnected-(J1-Pad6)") (class "Default")
      (node (ref "J1") (pin "6") (pinfunction "6_6") (pintype "bidirectional"))
    )
    (net (code "60") (name "unconnected-(J1-Pad7)") (class "Default")
      (node (ref "J1") (pin "7") (pinfunction "7_7") (pintype "bidirectional"))
    )
    (net (code "61") (name "unconnected-(J2-PadA8)") (class "Default")
      (node (ref "J2") (pin "A8") (pinfunction "A8_A8") (pintype "bidirectional"))
    )
    (net (code "62") (name "unconnected-(J2-PadB8)") (class "Default")
      (node (ref "J2") (pin "B8") (pinfunction "B8_B8") (pintype "bidirectional"))
    )
    (net (code "63") (name "unconnected-(J4-DAT1-PadP8)") (class "Default")
      (node (ref "J4") (pin "P8") (pinfunction "DAT1_P8") (pintype "bidirectional"))
    )
    (net (code "64") (name "unconnected-(J4-DAT2-PadP1)") (class "Default")
      (node (ref "J4") (pin "P1") (pinfunction "DAT2_P1") (pintype "bidirectional"))
    )
    (net (code "65") (name "unconnected-(J4-DETECTION_1-PadS1)") (class "Default")
      (node (ref "J4") (pin "S1") (pinfunction "DETECTION_1_S1") (pintype "bidirectional"))
    )
    (net (code "66") (name "unconnected-(J4-DETECTION_2-PadS2)") (class "Default")
      (node (ref "J4") (pin "S2") (pinfunction "DETECTION_2_S2") (pintype "bidirectional"))
    )
    (net (code "67") (name "unconnected-(U2-NC-Pad22)") (class "Default")
      (node (ref "U2") (pin "22") (pinfunction "NC_22") (pintype "no_connect"))
    )
    (net (code "68") (name "unconnected-(U4-~{ALERT}-Pad5)") (class "Default")
      (node (ref "U4") (pin "5") (pinfunction "~{ALERT}_5") (pintype "output"))
    )
  )
)
